# 4-ADC.net
KiCad netlist of a schematic drawn in Altium Designer
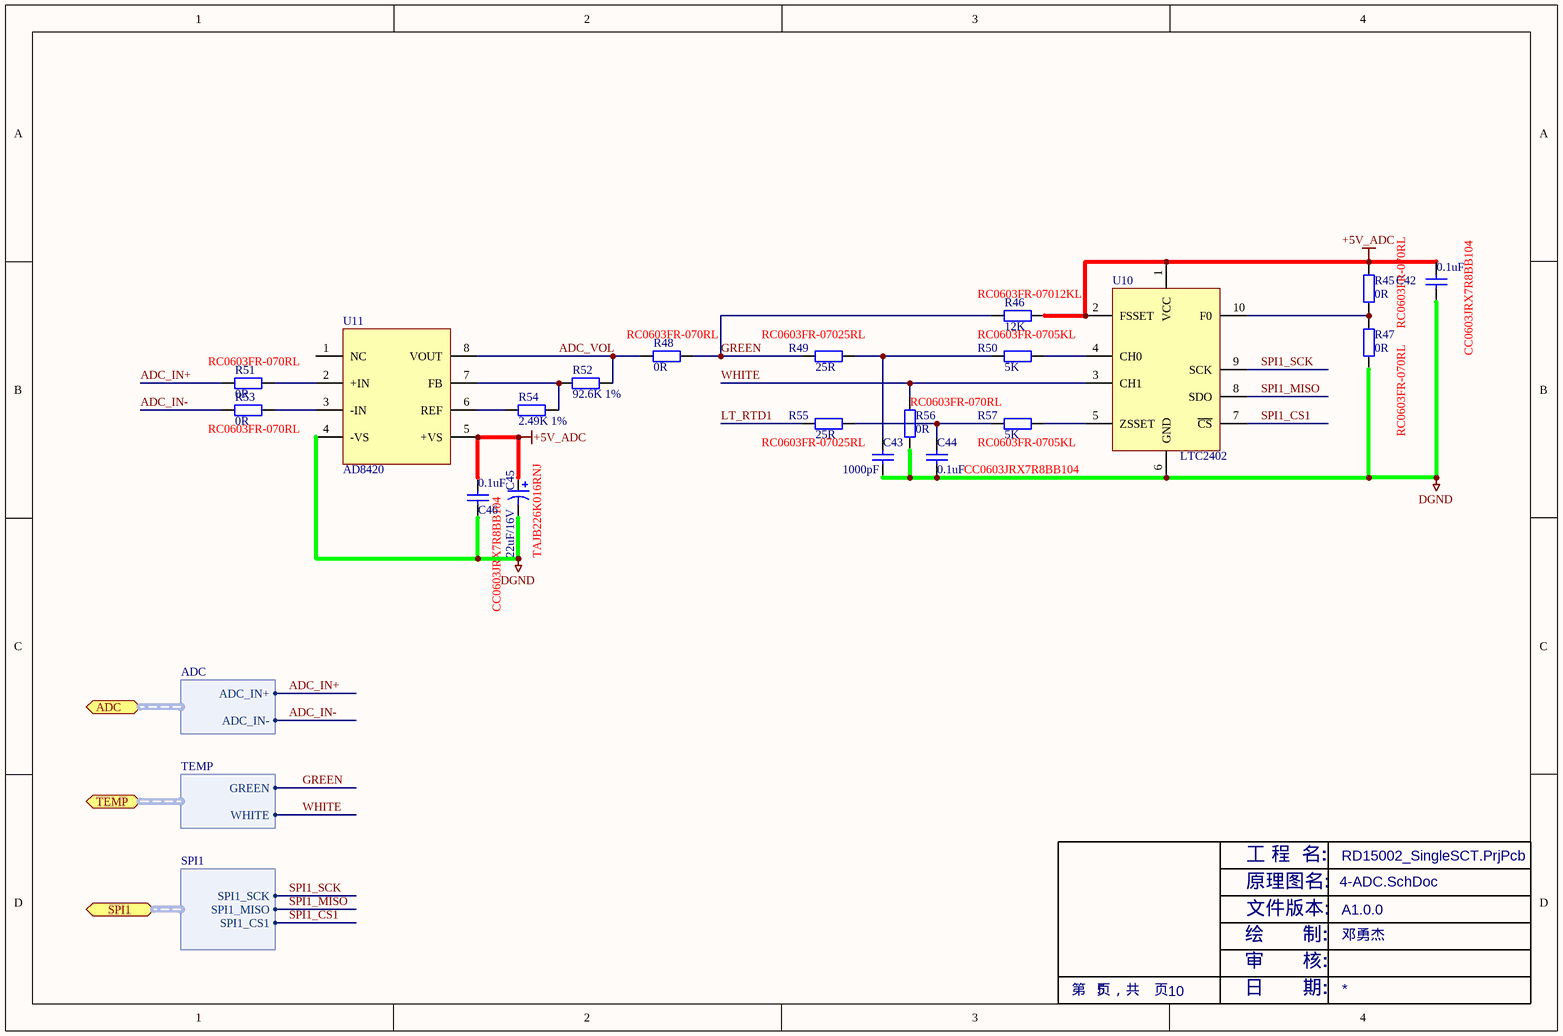
[diagram p0: 4-ADC.SchDoc]

(export (version "E")
  (design (tool "Eeschema 10.0.6"))
  (components
    (comp (ref "C42")
      (value "0.1uF")
      (footprint "CC0603")
      (description "Capacitor")
      (fields (field (name "TYPE NO.") "CC0603JRX7R8BB104"))
      (libsource (lib "Miscellaneous Devices") (part "Cap"))
    )
    (comp (ref "C43")
      (value "1000pF")
      (footprint "CC0603")
      (description "Capacitor")
      (libsource (lib "Miscellaneous Devices") (part "Cap"))
    )
    (comp (ref "C44")
      (value "0.1uF")
      (footprint "CC0603")
      (description "Capacitor")
      (fields (field (name "TYPE NO.") "CC0603JRX7R8BB104"))
      (libsource (lib "Miscellaneous Devices") (part "Cap"))
    )
    (comp (ref "C45")
      (value "22uF/16V")
      (footprint "CB3528")
      (description "Polarized Capacitor (Radial)")
      (fields (field (name "PART NO.") "TAJB226K016RNJ"))
      (libsource (lib "Miscellaneous Devices") (part "Cap Pol1"))
    )
    (comp (ref "C46")
      (value "0.1uF")
      (footprint "CC0603")
      (description "Capacitor")
      (fields (field (name "TYPE NO.") "CC0603JRX7R8BB104"))
      (libsource (lib "Miscellaneous Devices") (part "Cap"))
    )
    (comp (ref "R45")
      (value "0R")
      (footprint "CC0603")
      (description "Resistor")
      (fields (field (name "TYPE NO.") "RC0603FR-070RL"))
      (libsource (lib "") (part "Res2_2"))
    )
    (comp (ref "R46")
      (value "12K")
      (footprint "CC0603")
      (description "Resistor")
      (fields (field (name "TYPE NO.") "RC0603FR-07012KL"))
      (libsource (lib "") (part "Res2_1"))
    )
    (comp (ref "R47")
      (value "0R")
      (footprint "CC0603")
      (description "Resistor")
      (fields (field (name "TYPE NO.") "RC0603FR-070RL"))
      (libsource (lib "") (part "Res2_2"))
    )
    (comp (ref "R48")
      (value "0R")
      (footprint "CC0603")
      (description "Resistor")
      (fields (field (name "TYPE NO.") "RC0603FR-070RL"))
      (libsource (lib "Miscellaneous Devices") (part "Res2"))
    )
    (comp (ref "R49")
      (value "25R")
      (footprint "CC0603")
      (description "Resistor")
      (fields (field (name "TYPE NO.") "RC0603FR-07025RL"))
      (libsource (lib "Miscellaneous Devices") (part "Res2"))
    )
    (comp (ref "R50")
      (value "5K")
      (footprint "CC0603")
      (description "Resistor")
      (fields (field (name "TYPE NO.") "RC0603FR-0705KL"))
      (libsource (lib "Miscellaneous Devices") (part "Res2"))
    )
    (comp (ref "R51")
      (value "0R")
      (footprint "CC0603")
      (description "Resistor")
      (fields (field (name "TYPE NO.") "RC0603FR-070RL"))
      (libsource (lib "Miscellaneous Devices") (part "Res2"))
    )
    (comp (ref "R52")
      (value "92.6K 1%")
      (footprint "CC0603")
      (description "Resistor")
      (fields (field (name "PUBLISHER") "Altium Limited"))
      (libsource (lib "Miscellaneous Devices") (part "Res2"))
    )
    (comp (ref "R53")
      (value "0R")
      (footprint "CC0603")
      (description "Resistor")
      (fields (field (name "TYPE NO.") "RC0603FR-070RL"))
      (libsource (lib "Miscellaneous Devices") (part "Res2"))
    )
    (comp (ref "R54")
      (value "2.49K 1%")
      (footprint "CC0603")
      (description "Resistor")
      (fields (field (name "PUBLISHER") "Altium Limited"))
      (libsource (lib "Miscellaneous Devices") (part "Res2"))
    )
    (comp (ref "R55")
      (value "25R")
      (footprint "CC0603")
      (description "Resistor")
      (fields (field (name "TYPE NO.") "RC0603FR-07025RL"))
      (libsource (lib "Miscellaneous Devices") (part "Res2"))
    )
    (comp (ref "R56")
      (value "0R")
      (footprint "CC0603")
      (description "Resistor")
      (fields (field (name "TYPE NO.") "RC0603FR-070RL"))
      (libsource (lib "") (part "Res2_3"))
    )
    (comp (ref "R57")
      (value "5K")
      (footprint "CC0603")
      (description "Resistor")
      (fields (field (name "TYPE NO.") "RC0603FR-0705KL"))
      (libsource (lib "Miscellaneous Devices") (part "Res2"))
    )
    (comp (ref "U10") (value "LTC2402") (footprint "IC-SMT:MS10") (libsource (lib "IC") (part "LTC2402")))
    (comp (ref "U11") (value "AD8420") (footprint "MSOP8") (libsource (lib "IC") (part "AD8420")))
  )
  (nets
    (net (code "4") (name "+5V_ADC") (class "Default")
      (node (ref "C42") (pin "2") (pinfunction "2_2") (pintype "passive"))
      (node (ref "C45") (pin "1") (pinfunction "1_1") (pintype "passive"))
      (node (ref "C46") (pin "2") (pinfunction "2_2") (pintype "passive"))
      (node (ref "R45") (pin "1") (pinfunction "1_1") (pintype "passive"))
      (node (ref "R46") (pin "1") (pinfunction "1_1") (pintype "passive"))
      (node (ref "U10") (pin "1") (pinfunction "VCC_1") (pintype "passive"))
      (node (ref "U10") (pin "2") (pinfunction "FSSET_2") (pintype "passive"))
      (node (ref "U11") (pin "5") (pinfunction "+VS_5") (pintype "passive"))
    )
    (net (code "5") (name "/ADC_IN+") (class "Default")
      (node (ref "R51") (pin "1") (pinfunction "1_1") (pintype "passive"))
    )
    (net (code "6") (name "/ADC_IN-") (class "Default")
      (node (ref "R53") (pin "1") (pinfunction "1_1") (pintype "passive"))
    )
    (net (code "7") (name "/ADC_VOL") (class "Default")
      (node (ref "R48") (pin "1") (pinfunction "1_1") (pintype "passive"))
      (node (ref "R52") (pin "2") (pinfunction "2_2") (pintype "passive"))
      (node (ref "U11") (pin "8") (pinfunction "VOUT_8") (pintype "passive"))
    )
    (net (code "8") (name "/GREEN") (class "Default")
      (node (ref "R46") (pin "2") (pinfunction "2_2") (pintype "passive"))
      (node (ref "R48") (pin "2") (pinfunction "2_2") (pintype "passive"))
      (node (ref "R49") (pin "1") (pinfunction "1_1") (pintype "passive"))
    )
    (net (code "9") (name "/LT_RTD1") (class "Default")
      (node (ref "R55") (pin "1") (pinfunction "1_1") (pintype "passive"))
    )
    (net (code "10") (name "/SPI1_CS1") (class "Default")
      (node (ref "U10") (pin "7") (pinfunction "~{CS}_7") (pintype "passive"))
    )
    (net (code "11") (name "/SPI1_MISO") (class "Default")
      (node (ref "U10") (pin "8") (pinfunction "SDO_8") (pintype "passive"))
    )
    (net (code "12") (name "/SPI1_SCK") (class "Default")
      (node (ref "U10") (pin "9") (pinfunction "SCK_9") (pintype "passive"))
    )
    (net (code "13") (name "/WHITE") (class "Default")
      (node (ref "R56") (pin "2") (pinfunction "2_2") (pintype "passive"))
      (node (ref "U10") (pin "3") (pinfunction "CH1_3") (pintype "passive"))
    )
    (net (code "17") (name "DGND") (class "Default")
      (node (ref "C42") (pin "1") (pinfunction "1_1") (pintype "passive"))
      (node (ref "C43") (pin "1") (pinfunction "1_1") (pintype "passive"))
      (node (ref "C44") (pin "1") (pinfunction "1_1") (pintype "passive"))
      (node (ref "C45") (pin "2") (pinfunction "2_2") (pintype "passive"))
      (node (ref "C46") (pin "1") (pinfunction "1_1") (pintype "passive"))
      (node (ref "R47") (pin "2") (pinfunction "2_2") (pintype "passive"))
      (node (ref "R56") (pin "1") (pinfunction "1_1") (pintype "passive"))
      (node (ref "U10") (pin "6") (pinfunction "GND_6") (pintype "passive"))
      (node (ref "U11") (pin "4") (pinfunction "-VS_4") (pintype "passive"))
    )
    (net (code "18") (name "Net-(C43-Pad2)") (class "Default")
      (node (ref "C43") (pin "2") (pinfunction "2_2") (pintype "passive"))
      (node (ref "R49") (pin "2") (pinfunction "2_2") (pintype "passive"))
      (node (ref "R50") (pin "1") (pinfunction "1_1") (pintype "passive"))
    )
    (net (code "19") (name "Net-(C44-Pad2)") (class "Default")
      (node (ref "C44") (pin "2") (pinfunction "2_2") (pintype "passive"))
      (node (ref "R55") (pin "2") (pinfunction "2_2") (pintype "passive"))
      (node (ref "R57") (pin "1") (pinfunction "1_1") (pintype "passive"))
    )
    (net (code "20") (name "Net-(U10-CH0)") (class "Default")
      (node (ref "R50") (pin "2") (pinfunction "2_2") (pintype "passive"))
      (node (ref "U10") (pin "4") (pinfunction "CH0_4") (pintype "passive"))
    )
    (net (code "21") (name "Net-(U10-F0)") (class "Default")
      (node (ref "R45") (pin "2") (pinfunction "2_2") (pintype "passive"))
      (node (ref "R47") (pin "1") (pinfunction "1_1") (pintype "passive"))
      (node (ref "U10") (pin "10") (pinfunction "F0_10") (pintype "passive"))
    )
    (net (code "22") (name "Net-(U10-ZSSET)") (class "Default")
      (node (ref "R57") (pin "2") (pinfunction "2_2") (pintype "passive"))
      (node (ref "U10") (pin "5") (pinfunction "ZSSET_5") (pintype "passive"))
    )
    (net (code "23") (name "Net-(U11-+IN)") (class "Default")
      (node (ref "R51") (pin "2") (pinfunction "2_2") (pintype "passive"))
      (node (ref "U11") (pin "2") (pinfunction "+IN_2") (pintype "passive"))
    )
    (net (code "24") (name "Net-(U11--IN)") (class "Default")
      (node (ref "R53") (pin "2") (pinfunction "2_2") (pintype "passive"))
      (node (ref "U11") (pin "3") (pinfunction "-IN_3") (pintype "passive"))
    )
    (net (code "25") (name "Net-(U11-FB)") (class "Default")
      (node (ref "R52") (pin "1") (pinfunction "1_1") (pintype "passive"))
      (node (ref "R54") (pin "2") (pinfunction "2_2") (pintype "passive"))
      (node (ref "U11") (pin "7") (pinfunction "FB_7") (pintype "passive"))
    )
    (net (code "26") (name "Net-(U11-REF)") (class "Default")
      (node (ref "R54") (pin "1") (pinfunction "1_1") (pintype "passive"))
      (node (ref "U11") (pin "6") (pinfunction "REF_6") (pintype "passive"))
    )
    (net (code "27") (name "unconnected-(U11-NC-Pad1)") (class "Default")
      (node (ref "U11") (pin "1") (pinfunction "NC_1") (pintype "passive"))
    )
  )
)
